# SCH_Sega_Pad_-_Amiga_Joystick_2022-07-28.net
KiCad netlist of a schematic drawn in EasyEDA
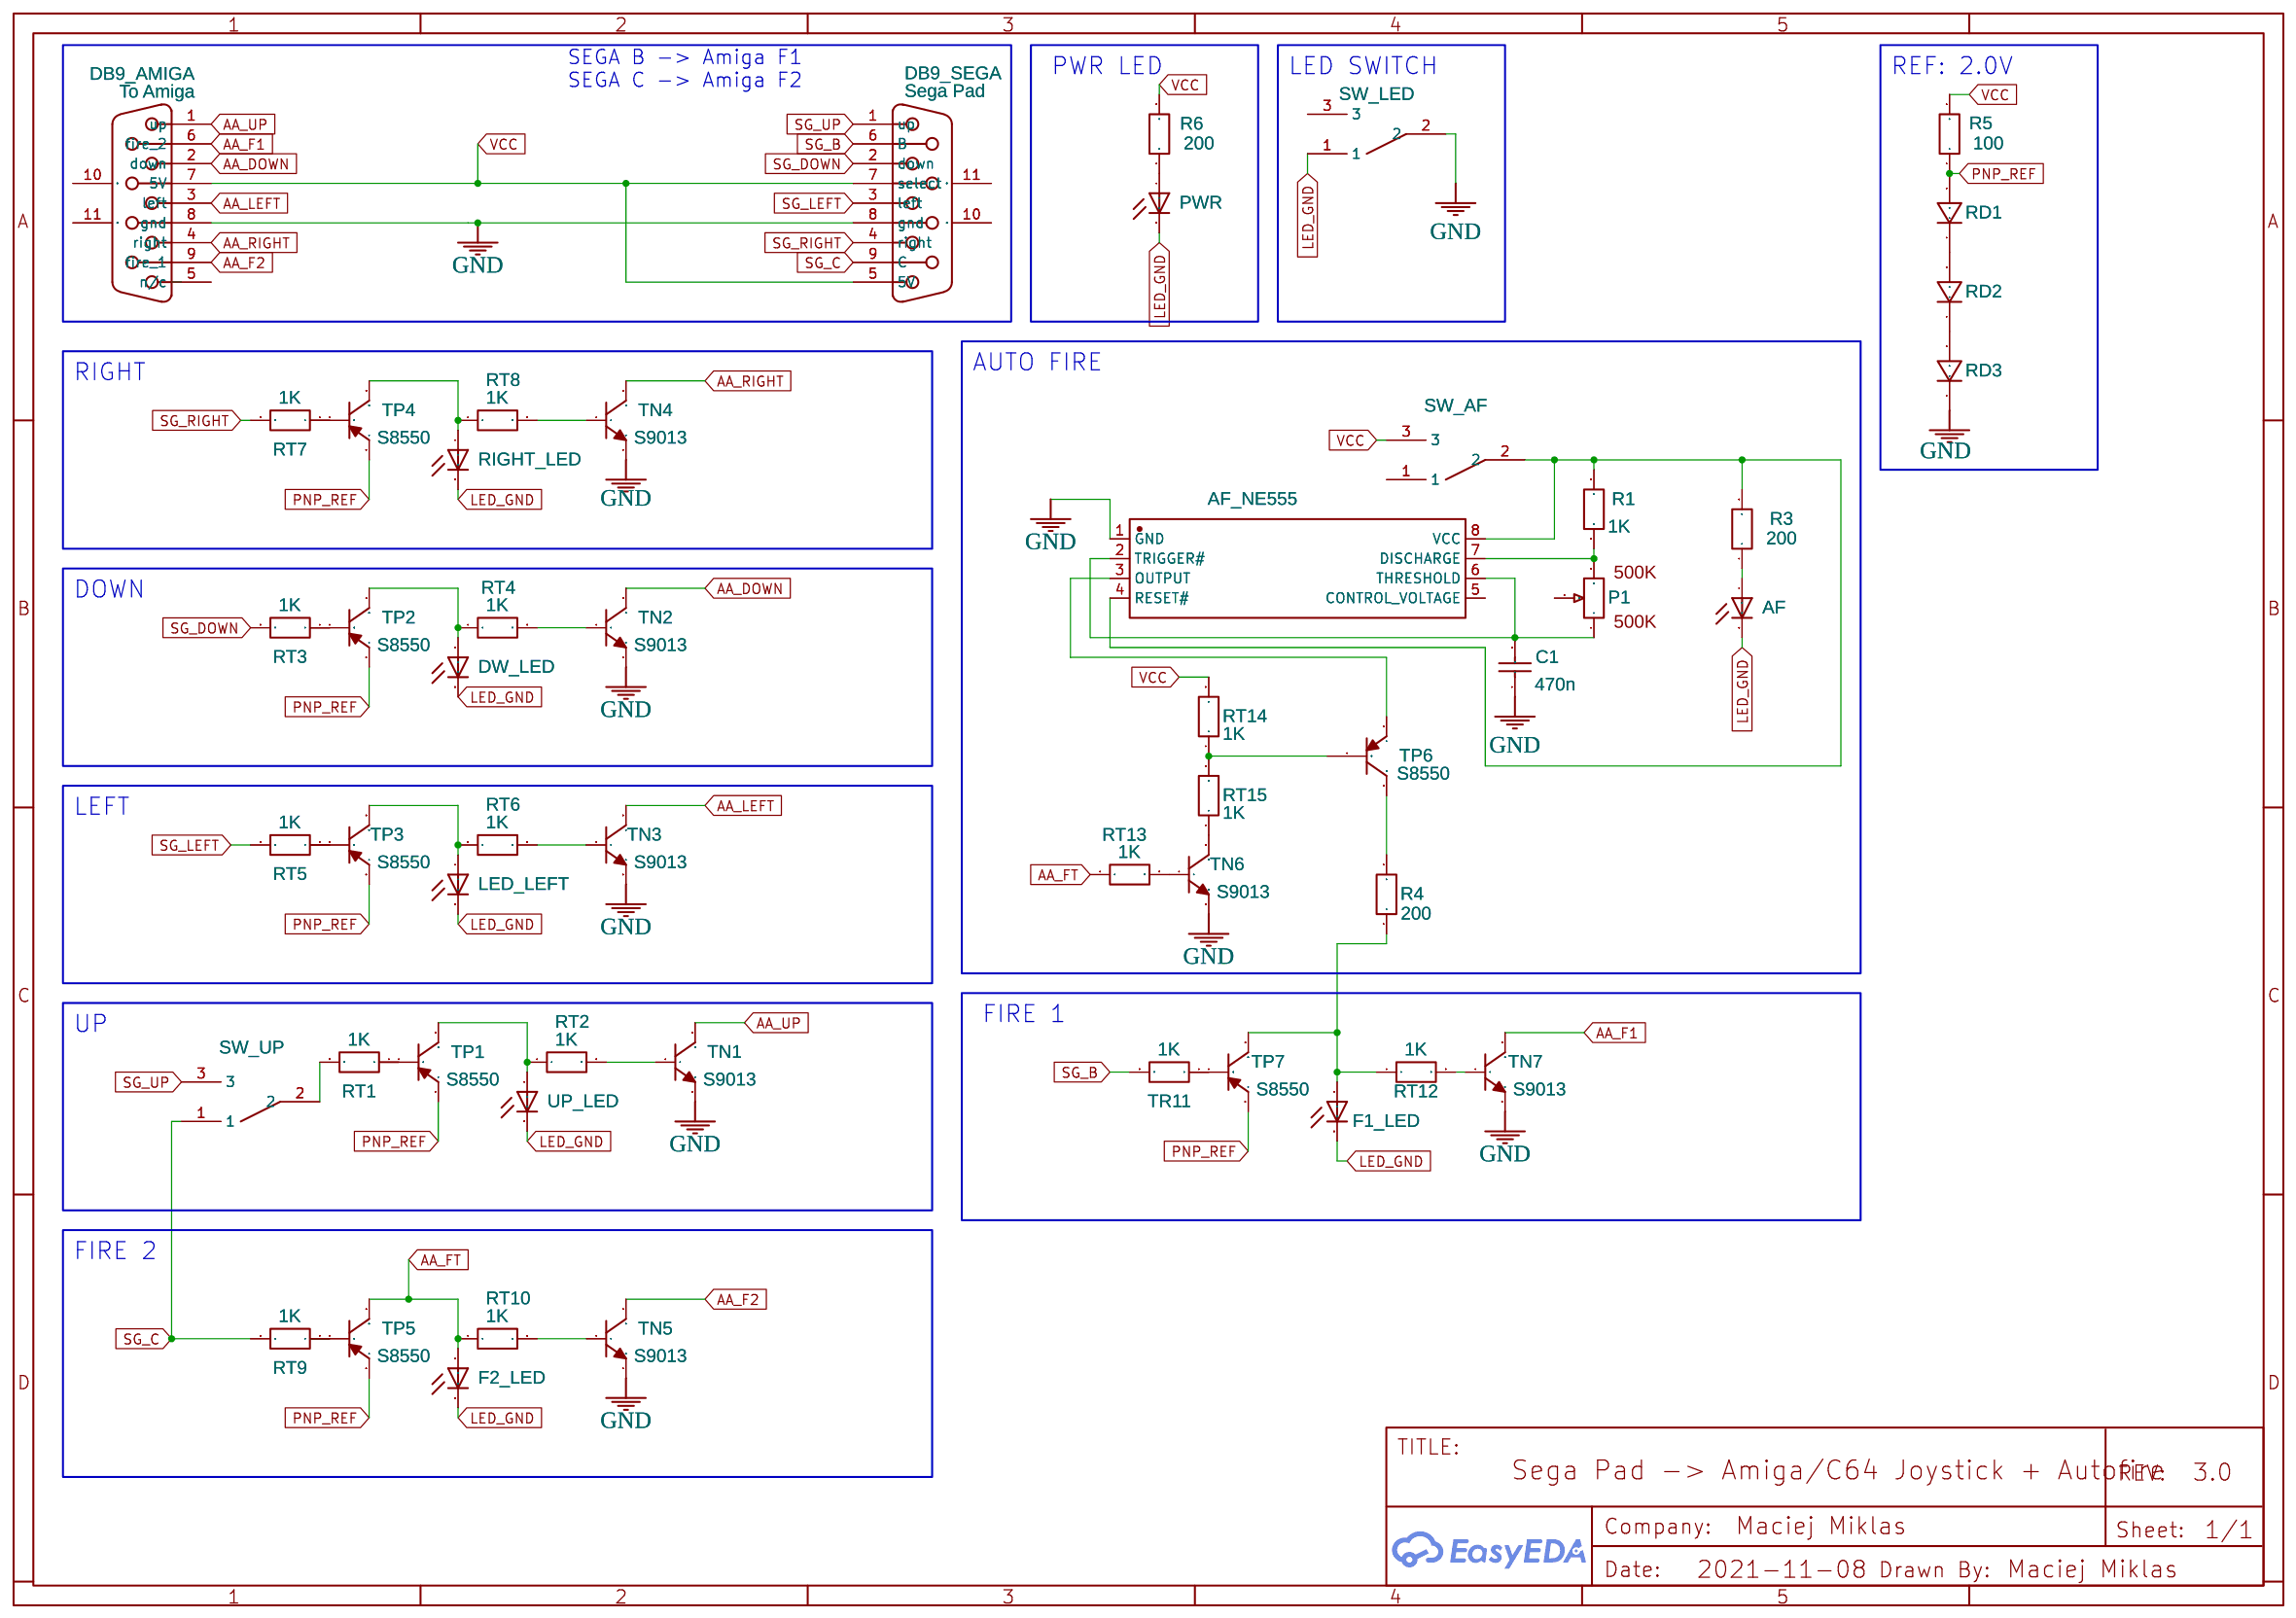
[diagram p0: schematic sheet]

(export (version "E")
  (design (tool "Eeschema 10.0.6"))
  (components
    (comp (ref "AF") (value "LED") (libsource (lib "") (part "LED_7")))
    (comp (ref "AF_555")
      (value "AF_NE555")
      (fields (field (name "BOM_Manufacturer Part") "NE555D") (field (name "BOM_Supplier Part") "C596355"))
      (libsource (lib "") (part "NE555D_C596355"))
    )
    (comp (ref "C1")
      (value "470n")
      (fields
        (field (name "BOM_Manufacturer Part") "CC0805KKX7R9BB105")
        (field (name "BOM_Supplier Part") "C91185")
      )
      (libsource (lib "") (part "CC0805KKX7R9BB105"))
    )
    (comp (ref "DB9_AMIGA")
      (value "To Amiga")
      (fields (field (name "BOM_Supplier Part") "C141882"))
      (libsource (lib "") (part "DB9_Female"))
    )
    (comp (ref "DB9_SEGA")
      (value "Sega Pad")
      (fields (field (name "BOM_Supplier Part") "C185657"))
      (libsource (lib "") (part "DB9_Male"))
    )
    (comp (ref "DW_LED") (value "LED") (libsource (lib "") (part "LED")))
    (comp (ref "F1_LED") (value "LED") (libsource (lib "") (part "LED_3")))
    (comp (ref "F2_LED") (value "LED") (libsource (lib "") (part "LED_2")))
    (comp (ref "LED_LEFT") (value "LED") (libsource (lib "") (part "LED_6")))
    (comp (ref "P1") (value "potentiometer") (libsource (lib "") (part "potentiometer")))
    (comp (ref "PWR") (value "LED") (libsource (lib "") (part "LED_4")))
    (comp (ref "R1")
      (value "1K")
      (fields
        (field (name "BOM_Manufacturer Part") "WR08X102 JTL")
        (field (name "BOM_Supplier Part") "C384174")
      )
      (libsource (lib "") (part "WR08X102 JTL_1"))
    )
    (comp (ref "R3")
      (value "200")
      (fields
        (field (name "BOM_Manufacturer Part") "WR08X102 JTL")
        (field (name "BOM_Supplier Part") "C384174")
      )
      (libsource (lib "") (part "WR08X102 JTL_1"))
    )
    (comp (ref "R4")
      (value "200")
      (fields
        (field (name "BOM_Manufacturer Part") "WR08X102 JTL")
        (field (name "BOM_Supplier Part") "C384174")
      )
      (libsource (lib "") (part "WR08X102 JTL_1"))
    )
    (comp (ref "R5")
      (value "100")
      (fields
        (field (name "BOM_Manufacturer Part") "WR08X102 JTL")
        (field (name "BOM_Supplier Part") "C384174")
      )
      (libsource (lib "") (part "WR08X102 JTL_1"))
    )
    (comp (ref "R6")
      (value "200")
      (fields
        (field (name "BOM_Manufacturer Part") "WR08X102 JTL")
        (field (name "BOM_Supplier Part") "C384174")
      )
      (libsource (lib "") (part "WR08X102 JTL_1"))
    )
    (comp (ref "RD1")
      (value "1N4148W-13-F")
      (fields (field (name "BOM_Supplier Part") "C112342"))
      (libsource (lib "") (part "1N4148W-13-F"))
    )
    (comp (ref "RD2")
      (value "1N4148W-13-F")
      (fields (field (name "BOM_Supplier Part") "C112342"))
      (libsource (lib "") (part "1N4148W-13-F"))
    )
    (comp (ref "RD3")
      (value "1N4148W-13-F")
      (fields (field (name "BOM_Supplier Part") "C112342"))
      (libsource (lib "") (part "1N4148W-13-F"))
    )
    (comp (ref "RIGHT_LED") (value "LED") (libsource (lib "") (part "LED_1")))
    (comp (ref "RT1")
      (value "1K")
      (fields
        (field (name "BOM_Manufacturer Part") "WR08X102 JTL")
        (field (name "BOM_Supplier Part") "C384174")
      )
      (libsource (lib "") (part "WR08X102 JTL_3"))
    )
    (comp (ref "RT2")
      (value "1K")
      (fields
        (field (name "BOM_Manufacturer Part") "WR08X102 JTL")
        (field (name "BOM_Supplier Part") "C384174")
      )
      (libsource (lib "") (part "WR08X102 JTL"))
    )
    (comp (ref "RT3")
      (value "1K")
      (fields
        (field (name "BOM_Manufacturer Part") "WR08X102 JTL")
        (field (name "BOM_Supplier Part") "C384174")
      )
      (libsource (lib "") (part "WR08X102 JTL_3"))
    )
    (comp (ref "RT4")
      (value "1K")
      (fields
        (field (name "BOM_Manufacturer Part") "WR08X102 JTL")
        (field (name "BOM_Supplier Part") "C384174")
      )
      (libsource (lib "") (part "WR08X102 JTL"))
    )
    (comp (ref "RT5")
      (value "1K")
      (fields
        (field (name "BOM_Manufacturer Part") "WR08X102 JTL")
        (field (name "BOM_Supplier Part") "C384174")
      )
      (libsource (lib "") (part "WR08X102 JTL_3"))
    )
    (comp (ref "RT6")
      (value "1K")
      (fields
        (field (name "BOM_Manufacturer Part") "WR08X102 JTL")
        (field (name "BOM_Supplier Part") "C384174")
      )
      (libsource (lib "") (part "WR08X102 JTL"))
    )
    (comp (ref "RT7")
      (value "1K")
      (fields
        (field (name "BOM_Manufacturer Part") "WR08X102 JTL")
        (field (name "BOM_Supplier Part") "C384174")
      )
      (libsource (lib "") (part "WR08X102 JTL_3"))
    )
    (comp (ref "RT8")
      (value "1K")
      (fields
        (field (name "BOM_Manufacturer Part") "WR08X102 JTL")
        (field (name "BOM_Supplier Part") "C384174")
      )
      (libsource (lib "") (part "WR08X102 JTL"))
    )
    (comp (ref "RT9")
      (value "1K")
      (fields
        (field (name "BOM_Manufacturer Part") "WR08X102 JTL")
        (field (name "BOM_Supplier Part") "C384174")
      )
      (libsource (lib "") (part "WR08X102 JTL_3"))
    )
    (comp (ref "RT10")
      (value "1K")
      (fields
        (field (name "BOM_Manufacturer Part") "WR08X102 JTL")
        (field (name "BOM_Supplier Part") "C384174")
      )
      (libsource (lib "") (part "WR08X102 JTL"))
    )
    (comp (ref "RT12")
      (value "1K")
      (fields
        (field (name "BOM_Manufacturer Part") "WR08X102 JTL")
        (field (name "BOM_Supplier Part") "C384174")
      )
      (libsource (lib "") (part "WR08X102 JTL"))
    )
    (comp (ref "RT13")
      (value "1K")
      (fields
        (field (name "BOM_Manufacturer Part") "WR08X102 JTL")
        (field (name "BOM_Supplier Part") "C384174")
      )
      (libsource (lib "") (part "WR08X102 JTL"))
    )
    (comp (ref "RT14")
      (value "1K")
      (fields
        (field (name "BOM_Manufacturer Part") "WR08X102 JTL")
        (field (name "BOM_Supplier Part") "C384174")
      )
      (libsource (lib "") (part "WR08X102 JTL_2"))
    )
    (comp (ref "RT15")
      (value "1K")
      (fields
        (field (name "BOM_Manufacturer Part") "WR08X102 JTL")
        (field (name "BOM_Supplier Part") "C384174")
      )
      (libsource (lib "") (part "WR08X102 JTL_2"))
    )
    (comp (ref "SW_AF") (value "1P2T") (libsource (lib "") (part "1P2T_2")))
    (comp (ref "SW_LED") (value "1P2T") (libsource (lib "") (part "1P2T_1")))
    (comp (ref "SW_UP") (value "1P2T") (libsource (lib "") (part "1P2T")))
    (comp (ref "TN1")
      (value "S9013")
      (fields
        (field (name "BOM_Manufacturer Part") "S9013 120-200")
        (field (name "BOM_Supplier Part") "C107404")
      )
      (libsource (lib "") (part "S9013 120-200"))
    )
    (comp (ref "TN2")
      (value "S9013")
      (fields
        (field (name "BOM_Manufacturer Part") "S9013 120-200")
        (field (name "BOM_Supplier Part") "C107404")
      )
      (libsource (lib "") (part "S9013 120-200"))
    )
    (comp (ref "TN3")
      (value "S9013")
      (fields
        (field (name "BOM_Manufacturer Part") "S9013 120-200")
        (field (name "BOM_Supplier Part") "C107404")
      )
      (libsource (lib "") (part "S9013 120-200"))
    )
    (comp (ref "TN4")
      (value "S9013")
      (fields
        (field (name "BOM_Manufacturer Part") "S9013 120-200")
        (field (name "BOM_Supplier Part") "C107404")
      )
      (libsource (lib "") (part "S9013 120-200"))
    )
    (comp (ref "TN5")
      (value "S9013")
      (fields
        (field (name "BOM_Manufacturer Part") "S9013 120-200")
        (field (name "BOM_Supplier Part") "C107404")
      )
      (libsource (lib "") (part "S9013 120-200"))
    )
    (comp (ref "TN6")
      (value "S9013")
      (fields
        (field (name "BOM_Manufacturer Part") "S9013 120-200")
        (field (name "BOM_Supplier Part") "C107404")
      )
      (libsource (lib "") (part "S9013 120-200"))
    )
    (comp (ref "TN7")
      (value "S9013")
      (fields
        (field (name "BOM_Manufacturer Part") "S9013 120-200")
        (field (name "BOM_Supplier Part") "C107404")
      )
      (libsource (lib "") (part "S9013 120-200"))
    )
    (comp (ref "TP1")
      (value "S8550")
      (fields (field (name "BOM_Supplier Part") "C2828467"))
      (libsource (lib "") (part "S8550_C2828467"))
    )
    (comp (ref "TP2")
      (value "S8550")
      (fields (field (name "BOM_Supplier Part") "C2828467"))
      (libsource (lib "") (part "S8550_C2828467"))
    )
    (comp (ref "TP3")
      (value "S8550")
      (fields (field (name "BOM_Supplier Part") "C2828467"))
      (libsource (lib "") (part "S8550_C2828467"))
    )
    (comp (ref "TP4")
      (value "S8550")
      (fields (field (name "BOM_Supplier Part") "C2828467"))
      (libsource (lib "") (part "S8550_C2828467"))
    )
    (comp (ref "TP5")
      (value "S8550")
      (fields (field (name "BOM_Supplier Part") "C2828467"))
      (libsource (lib "") (part "S8550_C2828467"))
    )
    (comp (ref "TP6")
      (value "S8550")
      (fields (field (name "BOM_Supplier Part") "C2828467"))
      (libsource (lib "") (part "S8550_C2828467_1"))
    )
    (comp (ref "TP7")
      (value "S8550")
      (fields (field (name "BOM_Supplier Part") "C2828467"))
      (libsource (lib "") (part "S8550_C2828467"))
    )
    (comp (ref "TR11")
      (value "1K")
      (fields
        (field (name "BOM_Manufacturer Part") "WR08X102 JTL")
        (field (name "BOM_Supplier Part") "C384174")
      )
      (libsource (lib "") (part "WR08X102 JTL_4"))
    )
    (comp (ref "UP_LED") (value "LED") (libsource (lib "") (part "LED_5")))
  )
  (nets
    (net (code "1") (name "AA_DOWN") (class "Default")
      (node (ref "DB9_AMIGA") (pin "2") (pinfunction "down_2") (pintype "input"))
      (node (ref "TN2") (pin "3") (pinfunction "3_3") (pintype "input"))
    )
    (net (code "2") (name "AA_F1") (class "Default")
      (node (ref "DB9_AMIGA") (pin "6") (pinfunction "fire_2_6") (pintype "input"))
      (node (ref "TN7") (pin "3") (pinfunction "3_3") (pintype "input"))
    )
    (net (code "3") (name "AA_F2") (class "Default")
      (node (ref "DB9_AMIGA") (pin "9") (pinfunction "fire_1_9") (pintype "input"))
      (node (ref "TN5") (pin "3") (pinfunction "3_3") (pintype "input"))
    )
    (net (code "4") (name "AA_FT") (class "Default")
      (node (ref "F2_LED") (pin "A") (pinfunction "A_A") (pintype "unspecified"))
      (node (ref "RT10") (pin "1") (pinfunction "1_1") (pintype "unspecified"))
      (node (ref "RT13") (pin "1") (pinfunction "1_1") (pintype "unspecified"))
      (node (ref "TP5") (pin "3") (pinfunction "C_3") (pintype "unspecified"))
    )
    (net (code "5") (name "AA_LEFT") (class "Default")
      (node (ref "DB9_AMIGA") (pin "3") (pinfunction "left_3") (pintype "input"))
      (node (ref "TN3") (pin "3") (pinfunction "3_3") (pintype "input"))
    )
    (net (code "6") (name "AA_RIGHT") (class "Default")
      (node (ref "DB9_AMIGA") (pin "4") (pinfunction "right_4") (pintype "input"))
      (node (ref "TN4") (pin "3") (pinfunction "3_3") (pintype "input"))
    )
    (net (code "7") (name "AA_UP") (class "Default")
      (node (ref "DB9_AMIGA") (pin "1") (pinfunction "up_1") (pintype "input"))
      (node (ref "TN1") (pin "3") (pinfunction "3_3") (pintype "input"))
    )
    (net (code "8") (name "GND") (class "Default")
      (node (ref "AF_555") (pin "1") (pinfunction "GND_1") (pintype "unspecified"))
      (node (ref "C1") (pin "1") (pinfunction "1_1") (pintype "input"))
      (node (ref "DB9_AMIGA") (pin "8") (pinfunction "gnd_8") (pintype "input"))
      (node (ref "DB9_SEGA") (pin "8") (pinfunction "gnd_8") (pintype "input"))
      (node (ref "RD3") (pin "1") (pinfunction "1_1") (pintype "unspecified"))
      (node (ref "SW_LED") (pin "2") (pinfunction "2_2") (pintype "unspecified"))
      (node (ref "TN1") (pin "2") (pinfunction "2_2") (pintype "input"))
      (node (ref "TN2") (pin "2") (pinfunction "2_2") (pintype "input"))
      (node (ref "TN3") (pin "2") (pinfunction "2_2") (pintype "input"))
      (node (ref "TN4") (pin "2") (pinfunction "2_2") (pintype "input"))
      (node (ref "TN5") (pin "2") (pinfunction "2_2") (pintype "input"))
      (node (ref "TN6") (pin "2") (pinfunction "2_2") (pintype "input"))
      (node (ref "TN7") (pin "2") (pinfunction "2_2") (pintype "input"))
    )
    (net (code "9") (name "LED_GND") (class "Default")
      (node (ref "AF") (pin "C") (pinfunction "C_C") (pintype "unspecified"))
      (node (ref "DW_LED") (pin "C") (pinfunction "C_C") (pintype "unspecified"))
      (node (ref "F1_LED") (pin "C") (pinfunction "C_C") (pintype "unspecified"))
      (node (ref "F2_LED") (pin "C") (pinfunction "C_C") (pintype "unspecified"))
      (node (ref "LED_LEFT") (pin "C") (pinfunction "C_C") (pintype "unspecified"))
      (node (ref "PWR") (pin "C") (pinfunction "C_C") (pintype "unspecified"))
      (node (ref "RIGHT_LED") (pin "C") (pinfunction "C_C") (pintype "unspecified"))
      (node (ref "SW_LED") (pin "1") (pinfunction "1_1") (pintype "unspecified"))
      (node (ref "UP_LED") (pin "C") (pinfunction "C_C") (pintype "unspecified"))
    )
    (net (code "10") (name "Net-(AF-PadA)") (class "Default")
      (node (ref "AF") (pin "A") (pinfunction "A_A") (pintype "unspecified"))
      (node (ref "R3") (pin "1") (pinfunction "1_1") (pintype "unspecified"))
    )
    (net (code "11") (name "Net-(AF_555-DISCHARGE)") (class "Default")
      (node (ref "AF_555") (pin "7") (pinfunction "DISCHARGE_7") (pintype "unspecified"))
      (node (ref "P1") (pin "3") (pinfunction "3_3") (pintype "input"))
      (node (ref "R1") (pin "1") (pinfunction "1_1") (pintype "unspecified"))
    )
    (net (code "12") (name "Net-(AF_555-OUTPUT)") (class "Default")
      (node (ref "AF_555") (pin "3") (pinfunction "OUTPUT_3") (pintype "unspecified"))
      (node (ref "TP6") (pin "2") (pinfunction "E_2") (pintype "unspecified"))
    )
    (net (code "13") (name "Net-(AF_555-RESET#)") (class "Default")
      (node (ref "AF_555") (pin "4") (pinfunction "RESET#_4") (pintype "unspecified"))
      (node (ref "AF_555") (pin "8") (pinfunction "VCC_8") (pintype "unspecified"))
      (node (ref "R1") (pin "2") (pinfunction "2_2") (pintype "unspecified"))
      (node (ref "R3") (pin "2") (pinfunction "2_2") (pintype "unspecified"))
      (node (ref "SW_AF") (pin "2") (pinfunction "2_2") (pintype "unspecified"))
    )
    (net (code "14") (name "Net-(AF_555-THRESHOLD)") (class "Default")
      (node (ref "AF_555") (pin "2") (pinfunction "TRIGGER#_2") (pintype "unspecified"))
      (node (ref "AF_555") (pin "6") (pinfunction "THRESHOLD_6") (pintype "unspecified"))
      (node (ref "C1") (pin "2") (pinfunction "2_2") (pintype "input"))
      (node (ref "P1") (pin "1") (pinfunction "1_1") (pintype "input"))
    )
    (net (code "15") (name "Net-(PWR-PadA)") (class "Default")
      (node (ref "PWR") (pin "A") (pinfunction "A_A") (pintype "unspecified"))
      (node (ref "R6") (pin "1") (pinfunction "1_1") (pintype "unspecified"))
    )
    (net (code "16") (name "Net-(RD1-Pad1)") (class "Default")
      (node (ref "RD1") (pin "1") (pinfunction "1_1") (pintype "unspecified"))
      (node (ref "RD2") (pin "2") (pinfunction "2_2") (pintype "unspecified"))
    )
    (net (code "17") (name "Net-(RD2-Pad1)") (class "Default")
      (node (ref "RD2") (pin "1") (pinfunction "1_1") (pintype "unspecified"))
      (node (ref "RD3") (pin "2") (pinfunction "2_2") (pintype "unspecified"))
    )
    (net (code "18") (name "Net-(RT1-Pad2)") (class "Default")
      (node (ref "RT1") (pin "2") (pinfunction "2_2") (pintype "unspecified"))
      (node (ref "SW_UP") (pin "2") (pinfunction "2_2") (pintype "unspecified"))
    )
    (net (code "19") (name "Net-(RT2-Pad2)") (class "Default")
      (node (ref "RT2") (pin "2") (pinfunction "2_2") (pintype "unspecified"))
      (node (ref "TN1") (pin "1") (pinfunction "1_1") (pintype "input"))
    )
    (net (code "20") (name "Net-(RT4-Pad2)") (class "Default")
      (node (ref "RT4") (pin "2") (pinfunction "2_2") (pintype "unspecified"))
      (node (ref "TN2") (pin "1") (pinfunction "1_1") (pintype "input"))
    )
    (net (code "21") (name "Net-(RT6-Pad2)") (class "Default")
      (node (ref "RT6") (pin "2") (pinfunction "2_2") (pintype "unspecified"))
      (node (ref "TN3") (pin "1") (pinfunction "1_1") (pintype "input"))
    )
    (net (code "22") (name "Net-(RT8-Pad2)") (class "Default")
      (node (ref "RT8") (pin "2") (pinfunction "2_2") (pintype "unspecified"))
      (node (ref "TN4") (pin "1") (pinfunction "1_1") (pintype "input"))
    )
    (net (code "23") (name "Net-(RT10-Pad2)") (class "Default")
      (node (ref "RT10") (pin "2") (pinfunction "2_2") (pintype "unspecified"))
      (node (ref "TN5") (pin "1") (pinfunction "1_1") (pintype "input"))
    )
    (net (code "24") (name "Net-(RT12-Pad2)") (class "Default")
      (node (ref "RT12") (pin "2") (pinfunction "2_2") (pintype "unspecified"))
      (node (ref "TN7") (pin "1") (pinfunction "1_1") (pintype "input"))
    )
    (net (code "25") (name "Net-(RT13-Pad2)") (class "Default")
      (node (ref "RT13") (pin "2") (pinfunction "2_2") (pintype "unspecified"))
      (node (ref "TN6") (pin "1") (pinfunction "1_1") (pintype "input"))
    )
    (net (code "26") (name "Net-(RT15-Pad1)") (class "Default")
      (node (ref "RT15") (pin "1") (pinfunction "1_1") (pintype "unspecified"))
      (node (ref "TN6") (pin "3") (pinfunction "3_3") (pintype "input"))
    )
    (net (code "27") (name "Net-(TP1-B)") (class "Default")
      (node (ref "RT1") (pin "1") (pinfunction "1_1") (pintype "unspecified"))
      (node (ref "TP1") (pin "1") (pinfunction "B_1") (pintype "unspecified"))
    )
    (net (code "28") (name "Net-(TP1-C)") (class "Default")
      (node (ref "RT2") (pin "1") (pinfunction "1_1") (pintype "unspecified"))
      (node (ref "TP1") (pin "3") (pinfunction "C_3") (pintype "unspecified"))
      (node (ref "UP_LED") (pin "A") (pinfunction "A_A") (pintype "unspecified"))
    )
    (net (code "29") (name "Net-(TP2-B)") (class "Default")
      (node (ref "RT3") (pin "1") (pinfunction "1_1") (pintype "unspecified"))
      (node (ref "TP2") (pin "1") (pinfunction "B_1") (pintype "unspecified"))
    )
    (net (code "30") (name "Net-(TP2-C)") (class "Default")
      (node (ref "DW_LED") (pin "A") (pinfunction "A_A") (pintype "unspecified"))
      (node (ref "RT4") (pin "1") (pinfunction "1_1") (pintype "unspecified"))
      (node (ref "TP2") (pin "3") (pinfunction "C_3") (pintype "unspecified"))
    )
    (net (code "31") (name "Net-(TP3-B)") (class "Default")
      (node (ref "RT5") (pin "1") (pinfunction "1_1") (pintype "unspecified"))
      (node (ref "TP3") (pin "1") (pinfunction "B_1") (pintype "unspecified"))
    )
    (net (code "32") (name "Net-(TP3-C)") (class "Default")
      (node (ref "LED_LEFT") (pin "A") (pinfunction "A_A") (pintype "unspecified"))
      (node (ref "RT6") (pin "1") (pinfunction "1_1") (pintype "unspecified"))
      (node (ref "TP3") (pin "3") (pinfunction "C_3") (pintype "unspecified"))
    )
    (net (code "33") (name "Net-(TP4-B)") (class "Default")
      (node (ref "RT7") (pin "1") (pinfunction "1_1") (pintype "unspecified"))
      (node (ref "TP4") (pin "1") (pinfunction "B_1") (pintype "unspecified"))
    )
    (net (code "34") (name "Net-(TP4-C)") (class "Default")
      (node (ref "RIGHT_LED") (pin "A") (pinfunction "A_A") (pintype "unspecified"))
      (node (ref "RT8") (pin "1") (pinfunction "1_1") (pintype "unspecified"))
      (node (ref "TP4") (pin "3") (pinfunction "C_3") (pintype "unspecified"))
    )
    (net (code "35") (name "Net-(TP5-B)") (class "Default")
      (node (ref "RT9") (pin "1") (pinfunction "1_1") (pintype "unspecified"))
      (node (ref "TP5") (pin "1") (pinfunction "B_1") (pintype "unspecified"))
    )
    (net (code "36") (name "Net-(TP6-B)") (class "Default")
      (node (ref "RT14") (pin "1") (pinfunction "1_1") (pintype "unspecified"))
      (node (ref "RT15") (pin "2") (pinfunction "2_2") (pintype "unspecified"))
      (node (ref "TP6") (pin "1") (pinfunction "B_1") (pintype "unspecified"))
    )
    (net (code "37") (name "Net-(TP6-C)") (class "Default")
      (node (ref "R4") (pin "2") (pinfunction "2_2") (pintype "unspecified"))
      (node (ref "TP6") (pin "3") (pinfunction "C_3") (pintype "unspecified"))
    )
    (net (code "38") (name "Net-(TP7-B)") (class "Default")
      (node (ref "TP7") (pin "1") (pinfunction "B_1") (pintype "unspecified"))
      (node (ref "TR11") (pin "1") (pinfunction "1_1") (pintype "unspecified"))
    )
    (net (code "39") (name "Net-(TP7-C)") (class "Default")
      (node (ref "F1_LED") (pin "A") (pinfunction "A_A") (pintype "unspecified"))
      (node (ref "R4") (pin "1") (pinfunction "1_1") (pintype "unspecified"))
      (node (ref "RT12") (pin "1") (pinfunction "1_1") (pintype "unspecified"))
      (node (ref "TP7") (pin "3") (pinfunction "C_3") (pintype "unspecified"))
    )
    (net (code "40") (name "PNP_REF") (class "Default")
      (node (ref "R5") (pin "1") (pinfunction "1_1") (pintype "unspecified"))
      (node (ref "RD1") (pin "2") (pinfunction "2_2") (pintype "unspecified"))
      (node (ref "TP1") (pin "2") (pinfunction "E_2") (pintype "unspecified"))
      (node (ref "TP2") (pin "2") (pinfunction "E_2") (pintype "unspecified"))
      (node (ref "TP3") (pin "2") (pinfunction "E_2") (pintype "unspecified"))
      (node (ref "TP4") (pin "2") (pinfunction "E_2") (pintype "unspecified"))
      (node (ref "TP5") (pin "2") (pinfunction "E_2") (pintype "unspecified"))
      (node (ref "TP7") (pin "2") (pinfunction "E_2") (pintype "unspecified"))
    )
    (net (code "41") (name "SG_B") (class "Default")
      (node (ref "DB9_SEGA") (pin "6") (pinfunction "B_6") (pintype "input"))
      (node (ref "TR11") (pin "2") (pinfunction "2_2") (pintype "unspecified"))
    )
    (net (code "42") (name "SG_C") (class "Default")
      (node (ref "DB9_SEGA") (pin "9") (pinfunction "C_9") (pintype "input"))
      (node (ref "RT9") (pin "2") (pinfunction "2_2") (pintype "unspecified"))
      (node (ref "SW_UP") (pin "1") (pinfunction "1_1") (pintype "unspecified"))
    )
    (net (code "43") (name "SG_DOWN") (class "Default")
      (node (ref "DB9_SEGA") (pin "2") (pinfunction "down_2") (pintype "input"))
      (node (ref "RT3") (pin "2") (pinfunction "2_2") (pintype "unspecified"))
    )
    (net (code "44") (name "SG_LEFT") (class "Default")
      (node (ref "DB9_SEGA") (pin "3") (pinfunction "left_3") (pintype "input"))
      (node (ref "RT5") (pin "2") (pinfunction "2_2") (pintype "unspecified"))
    )
    (net (code "45") (name "SG_RIGHT") (class "Default")
      (node (ref "DB9_SEGA") (pin "4") (pinfunction "right_4") (pintype "input"))
      (node (ref "RT7") (pin "2") (pinfunction "2_2") (pintype "unspecified"))
    )
    (net (code "46") (name "SG_UP") (class "Default")
      (node (ref "DB9_SEGA") (pin "1") (pinfunction "up_1") (pintype "input"))
      (node (ref "SW_UP") (pin "3") (pinfunction "3_3") (pintype "unspecified"))
    )
    (net (code "47") (name "VCC") (class "Default")
      (node (ref "DB9_AMIGA") (pin "7") (pinfunction "5V_7") (pintype "input"))
      (node (ref "DB9_SEGA") (pin "5") (pinfunction "5V_5") (pintype "input"))
      (node (ref "DB9_SEGA") (pin "7") (pinfunction "select_7") (pintype "input"))
      (node (ref "R5") (pin "2") (pinfunction "2_2") (pintype "unspecified"))
      (node (ref "R6") (pin "2") (pinfunction "2_2") (pintype "unspecified"))
      (node (ref "RT14") (pin "2") (pinfunction "2_2") (pintype "unspecified"))
      (node (ref "SW_AF") (pin "3") (pinfunction "3_3") (pintype "unspecified"))
    )
    (net (code "48") (name "unconnected-(AF_555-CONTROL_VOLTAGE-Pad5)") (class "Default")
      (node (ref "AF_555") (pin "5") (pinfunction "CONTROL_VOLTAGE_5") (pintype "unspecified"))
    )
    (net (code "49") (name "unconnected-(DB9_AMIGA-MH1-Pad10)") (class "Default")
      (node (ref "DB9_AMIGA") (pin "10") (pinfunction "MH1_10") (pintype "input"))
    )
    (net (code "50") (name "unconnected-(DB9_AMIGA-MH2-Pad11)") (class "Default")
      (node (ref "DB9_AMIGA") (pin "11") (pinfunction "MH2_11") (pintype "input"))
    )
    (net (code "51") (name "unconnected-(DB9_AMIGA-n{slash}c-Pad5)") (class "Default")
      (node (ref "DB9_AMIGA") (pin "5") (pinfunction "n/c_5") (pintype "input"))
    )
    (net (code "52") (name "unconnected-(DB9_SEGA-MH1-Pad10)") (class "Default")
      (node (ref "DB9_SEGA") (pin "10") (pinfunction "MH1_10") (pintype "input"))
    )
    (net (code "53") (name "unconnected-(DB9_SEGA-MH2-Pad11)") (class "Default")
      (node (ref "DB9_SEGA") (pin "11") (pinfunction "MH2_11") (pintype "input"))
    )
    (net (code "54") (name "unconnected-(P1-Pad2)") (class "Default")
      (node (ref "P1") (pin "2") (pinfunction "2_2") (pintype "input"))
    )
    (net (code "55") (name "unconnected-(SW_AF-Pad1)") (class "Default")
      (node (ref "SW_AF") (pin "1") (pinfunction "1_1") (pintype "unspecified"))
    )
    (net (code "56") (name "unconnected-(SW_LED-Pad3)") (class "Default")
      (node (ref "SW_LED") (pin "3") (pinfunction "3_3") (pintype "unspecified"))
    )
  )
)
